# MPR121-Cap-Touch-Keypad.net
KiCad netlist of a schematic drawn in EAGLE
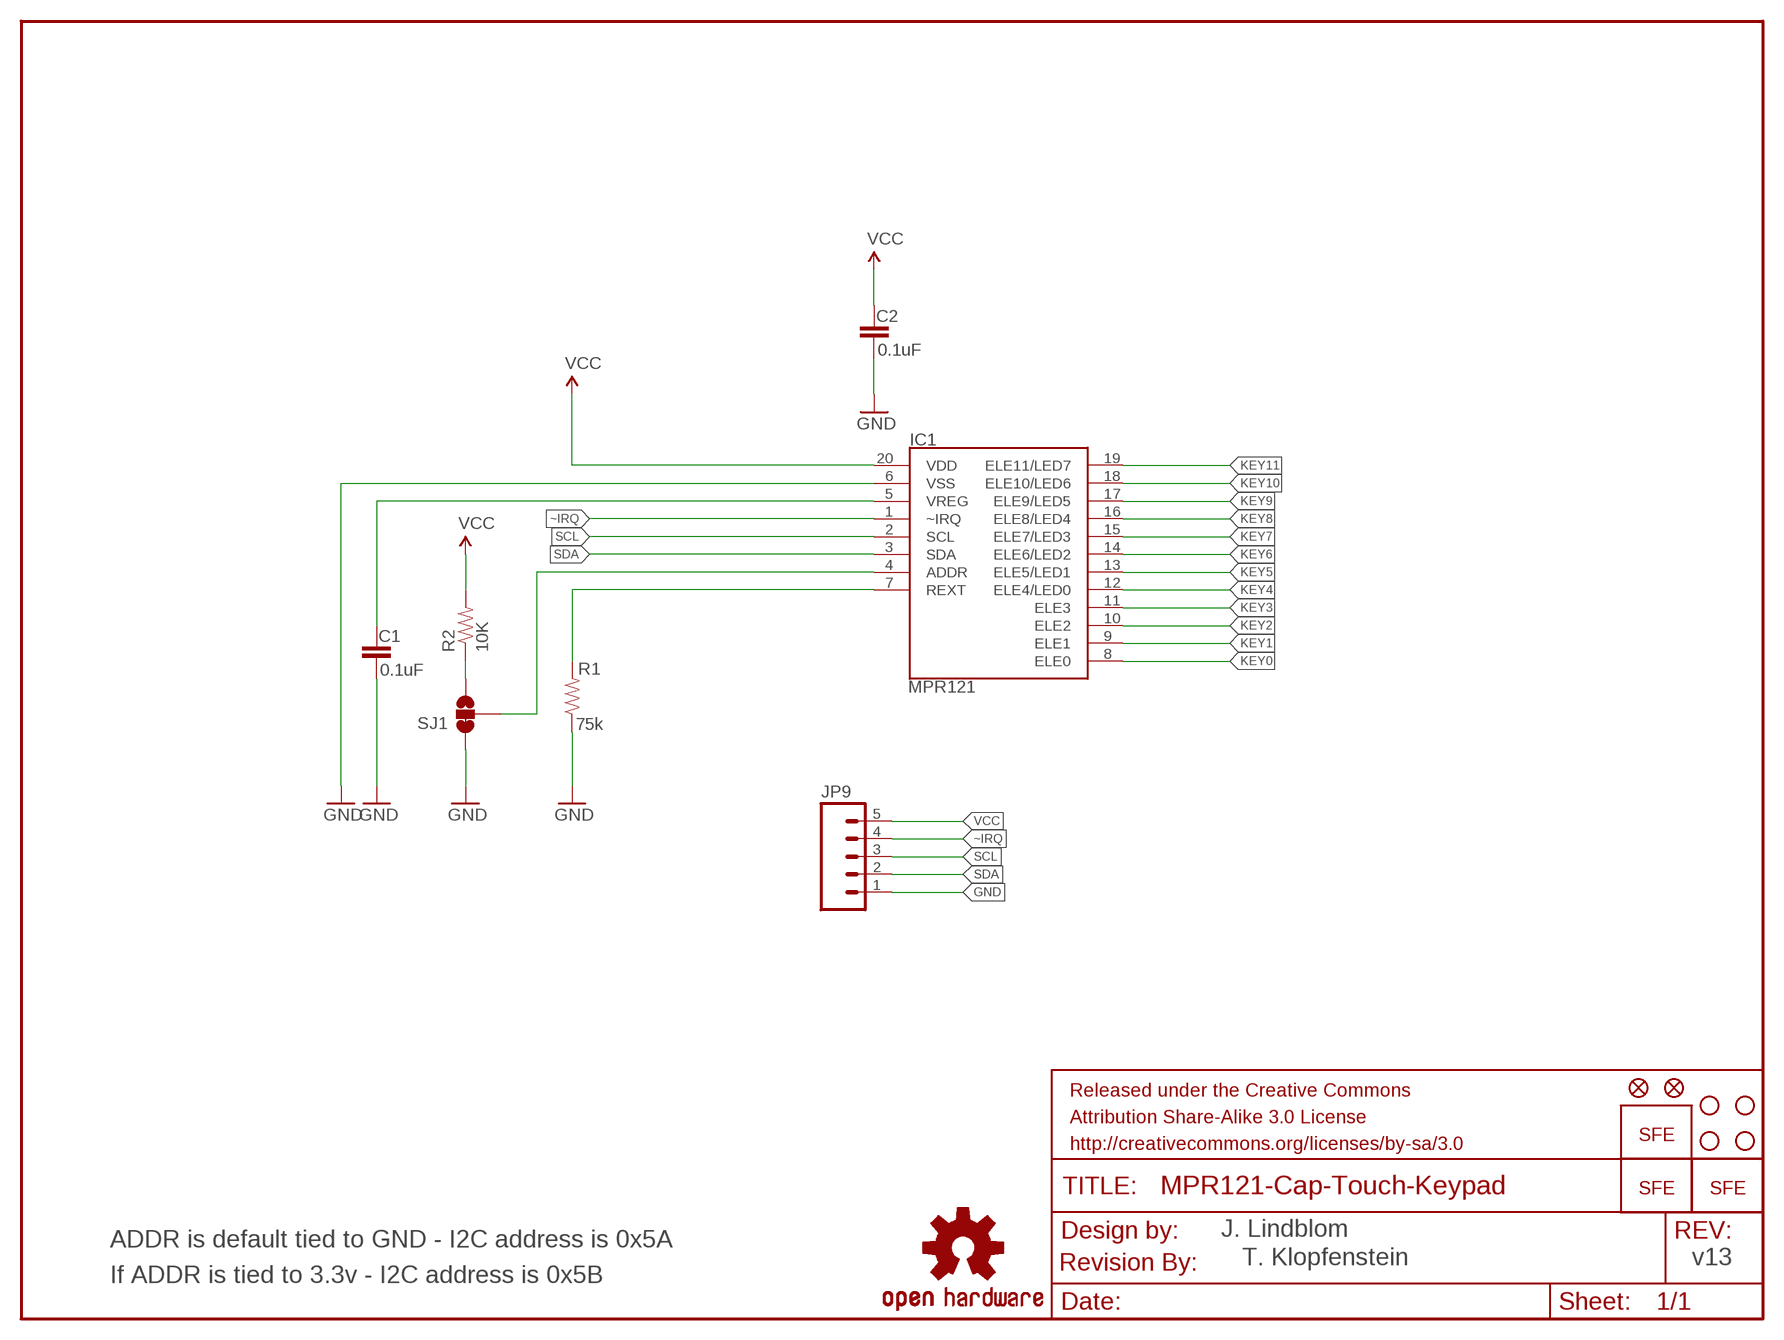
[diagram p0: schematic, sheet 1]

(export (version "E")
  (design (tool "Eeschema 10.0.6"))
  (components
    (comp (ref "C1")
      (value "0.1uF")
      (footprint "eagle-import:0603-CAP")
      (libsource (lib "eagle-import") (part "0.1UF-25V(+80/-20%)(0603)"))
    )
    (comp (ref "C2")
      (value "0.1uF")
      (footprint "eagle-import:0603-CAP")
      (libsource (lib "eagle-import") (part "0.1UF-25V(+80/-20%)(0603)"))
    )
    (comp (ref "FRAME1")
      (value "FRAME-LETTER")
      (footprint "eagle-import:CREATIVE_COMMONS")
      (libsource (lib "eagle-import") (part "FRAME-LETTER"))
    )
    (comp (ref "IC1")
      (value "MPR121")
      (footprint "eagle-import:QFN-20-0.4MM-V2")
      (libsource (lib "eagle-import") (part "MPR121V2"))
    )
    (comp (ref "JP1")
      (value "LOGO-SFENEW")
      (footprint "eagle-import:SFE-NEW-WEBLOGO")
      (libsource (lib "eagle-import") (part "LOGO-SFENEW"))
    )
    (comp (ref "JP2")
      (value "LOGO-SFESK")
      (footprint "eagle-import:SFE-LOGO-FLAME")
      (libsource (lib "eagle-import") (part "LOGO-SFESK"))
    )
    (comp (ref "JP3")
      (value "STAND-OFF")
      (footprint "eagle-import:STAND-OFF")
      (libsource (lib "eagle-import") (part "STAND-OFF"))
    )
    (comp (ref "JP4")
      (value "STAND-OFF")
      (footprint "eagle-import:STAND-OFF")
      (libsource (lib "eagle-import") (part "STAND-OFF"))
    )
    (comp (ref "JP5")
      (value "FIDUCIAL1X2")
      (footprint "eagle-import:FIDUCIAL-1X2")
      (libsource (lib "eagle-import") (part "FIDUCIAL1X2"))
    )
    (comp (ref "JP6")
      (value "LOGO-SFESK")
      (footprint "eagle-import:SFE-LOGO-FLAME")
      (libsource (lib "eagle-import") (part "LOGO-SFESK"))
    )
    (comp (ref "JP7")
      (value "STAND-OFF")
      (footprint "eagle-import:STAND-OFF")
      (libsource (lib "eagle-import") (part "STAND-OFF"))
    )
    (comp (ref "JP8")
      (value "STAND-OFF")
      (footprint "eagle-import:STAND-OFF")
      (libsource (lib "eagle-import") (part "STAND-OFF"))
    )
    (comp (ref "JP9")
      (value "M05PTH")
      (footprint "eagle-import:1X05")
      (libsource (lib "eagle-import") (part "M05PTH"))
    )
    (comp (ref "JP10")
      (value "FIDUCIAL1X2")
      (footprint "eagle-import:FIDUCIAL-1X2")
      (libsource (lib "eagle-import") (part "FIDUCIAL1X2"))
    )
    (comp (ref "LOGO1")
      (value "OSHW-LOGOL")
      (footprint "eagle-import:OSHW-LOGO-L")
      (libsource (lib "eagle-import") (part "OSHW-LOGOL"))
    )
    (comp (ref "R1")
      (value "75k")
      (footprint "eagle-import:0603-RES")
      (libsource (lib "eagle-import") (part "RESISTOR0603-RES"))
    )
    (comp (ref "R2")
      (value "10K")
      (footprint "eagle-import:0603-RES")
      (libsource (lib "eagle-import") (part "10KOHM1/10W1%(0603)0603"))
    )
    (comp (ref "SJ1")
      (value "SOLDERJUMPER_2WAYPASTE1&2")
      (footprint "eagle-import:SJ_3_PASTE1&2")
      (libsource (lib "eagle-import") (part "SOLDERJUMPER_2WAYPASTE1&2"))
    )
    (comp (ref "U$1")
      (value "REVISION")
      (footprint "eagle-import:REVISION")
      (libsource (lib "eagle-import") (part "REVISION"))
    )
  )
  (nets
    (net (code "1") (name "/~{IRQ}") (class "Default")
      (node (ref "IC1") (pin "1") (pinfunction "~{IRQ}_1") (pintype "bidirectional"))
      (node (ref "JP9") (pin "4") (pinfunction "4_4") (pintype "passive"))
    )
    (net (code "2") (name "GND") (class "Default")
      (node (ref "C1") (pin "2") (pinfunction "2_2") (pintype "passive"))
      (node (ref "C2") (pin "2") (pinfunction "2_2") (pintype "passive"))
      (node (ref "IC1") (pin "6") (pinfunction "VSS_6") (pintype "bidirectional"))
      (node (ref "JP9") (pin "1") (pinfunction "1_1") (pintype "passive"))
      (node (ref "R1") (pin "1") (pinfunction "1_1") (pintype "passive"))
      (node (ref "SJ1") (pin "1") (pinfunction "1_1") (pintype "passive"))
    )
    (net (code "3") (name "KEY0") (class "Default")
      (node (ref "IC1") (pin "8") (pinfunction "ELE0_8") (pintype "bidirectional"))
    )
    (net (code "4") (name "KEY1") (class "Default")
      (node (ref "IC1") (pin "9") (pinfunction "ELE1_9") (pintype "bidirectional"))
    )
    (net (code "5") (name "KEY2") (class "Default")
      (node (ref "IC1") (pin "10") (pinfunction "ELE2_10") (pintype "bidirectional"))
    )
    (net (code "6") (name "KEY3") (class "Default")
      (node (ref "IC1") (pin "11") (pinfunction "ELE3_11") (pintype "bidirectional"))
    )
    (net (code "7") (name "KEY4") (class "Default")
      (node (ref "IC1") (pin "12") (pinfunction "ELE4/LED0_12") (pintype "bidirectional"))
    )
    (net (code "8") (name "KEY5") (class "Default")
      (node (ref "IC1") (pin "13") (pinfunction "ELE5/LED1_13") (pintype "bidirectional"))
    )
    (net (code "9") (name "KEY6") (class "Default")
      (node (ref "IC1") (pin "14") (pinfunction "ELE6/LED2_14") (pintype "bidirectional"))
    )
    (net (code "10") (name "KEY7") (class "Default")
      (node (ref "IC1") (pin "15") (pinfunction "ELE7/LED3_15") (pintype "bidirectional"))
    )
    (net (code "11") (name "KEY8") (class "Default")
      (node (ref "IC1") (pin "16") (pinfunction "ELE8/LED4_16") (pintype "bidirectional"))
    )
    (net (code "12") (name "KEY9") (class "Default")
      (node (ref "IC1") (pin "17") (pinfunction "ELE9/LED5_17") (pintype "bidirectional"))
    )
    (net (code "13") (name "KEY10") (class "Default")
      (node (ref "IC1") (pin "18") (pinfunction "ELE10/LED6_18") (pintype "bidirectional"))
    )
    (net (code "14") (name "KEY11") (class "Default")
      (node (ref "IC1") (pin "19") (pinfunction "ELE11/LED7_19") (pintype "bidirectional"))
    )
    (net (code "15") (name "Net-(IC1-ADDR)") (class "Default")
      (node (ref "IC1") (pin "4") (pinfunction "ADDR_4") (pintype "bidirectional"))
      (node (ref "SJ1") (pin "2") (pinfunction "2_2") (pintype "passive"))
    )
    (net (code "16") (name "Net-(IC1-REXT)") (class "Default")
      (node (ref "IC1") (pin "7") (pinfunction "REXT_7") (pintype "bidirectional"))
      (node (ref "R1") (pin "2") (pinfunction "2_2") (pintype "passive"))
    )
    (net (code "17") (name "Net-(IC1-VREG)") (class "Default")
      (node (ref "C1") (pin "1") (pinfunction "1_1") (pintype "passive"))
      (node (ref "IC1") (pin "5") (pinfunction "VREG_5") (pintype "bidirectional"))
    )
    (net (code "18") (name "Net-(R2-Pad1)") (class "Default")
      (node (ref "R2") (pin "1") (pinfunction "1_1") (pintype "passive"))
      (node (ref "SJ1") (pin "3") (pinfunction "3_3") (pintype "passive"))
    )
    (net (code "19") (name "SCL") (class "Default")
      (node (ref "IC1") (pin "2") (pinfunction "SCL_2") (pintype "bidirectional"))
      (node (ref "JP9") (pin "3") (pinfunction "3_3") (pintype "passive"))
    )
    (net (code "20") (name "SDA") (class "Default")
      (node (ref "IC1") (pin "3") (pinfunction "SDA_3") (pintype "bidirectional"))
      (node (ref "JP9") (pin "2") (pinfunction "2_2") (pintype "passive"))
    )
    (net (code "21") (name "VCC") (class "Default")
      (node (ref "C2") (pin "1") (pinfunction "1_1") (pintype "passive"))
      (node (ref "IC1") (pin "20") (pinfunction "VDD_20") (pintype "bidirectional"))
      (node (ref "JP9") (pin "5") (pinfunction "5_5") (pintype "passive"))
      (node (ref "R2") (pin "2") (pinfunction "2_2") (pintype "passive"))
    )
  )
)
